# USB_Headers.net
KiCad netlist of a schematic drawn in Altium Designer
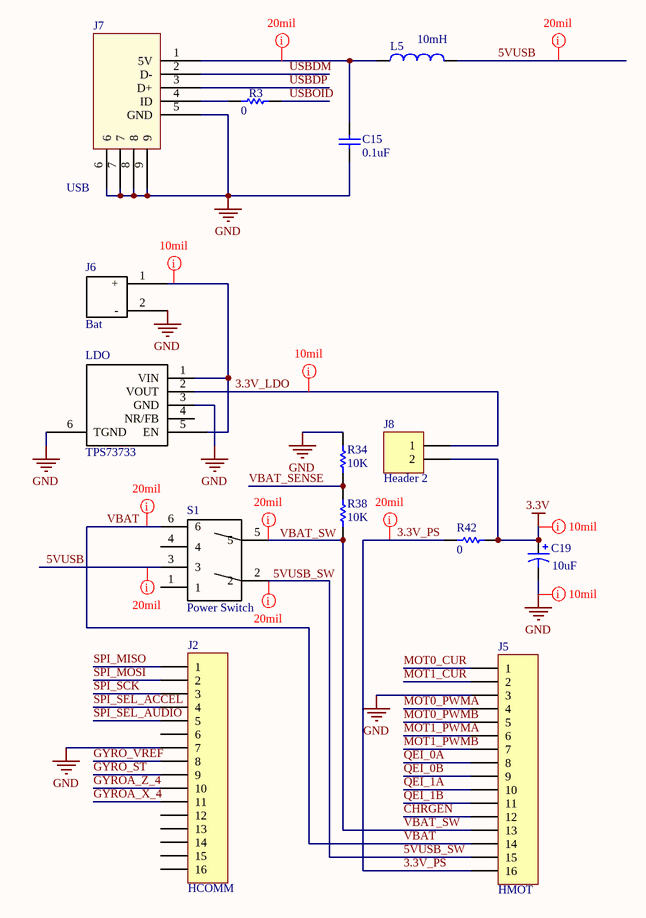
[diagram p0: USB_Headers.SchDoc]

(export (version "E")
  (design (tool "Eeschema 10.0.6"))
  (components
    (comp (ref "C15")
      (value "0.1uF")
      (footprint "CAPC1005L")
      (description "Capacitor")
      (fields (field (name "PUBLISHER") "Altium Limited"))
      (libsource (lib "Miscellaneous Devices") (part "Cap"))
    )
    (comp (ref "C19")
      (value "10uF")
      (footprint "CAPC3216L")
      (description "Polarized Capacitor (Surface Mount)")
      (fields (field (name "Comment") "Cap Pol3") (field (name "PUBLISHER") "Altium Limited"))
      (libsource (lib "Miscellaneous Devices") (part "Cap Pol3"))
    )
    (comp (ref "J2")
      (value "HCOMM")
      (footprint "HDR1X16")
      (description "Header, 16-Pin")
      (fields (field (name "PUBLISHER") "Altium Limited"))
      (libsource (lib "Miscellaneous Connectors") (part "Header 16"))
    )
    (comp (ref "J5")
      (value "HMOT")
      (footprint "HDR1X16")
      (description "Header, 16-Pin")
      (fields (field (name "PUBLISHER") "Altium Limited"))
      (libsource (lib "Miscellaneous Connectors") (part "Header 16"))
    )
    (comp (ref "J6")
      (value "Bat")
      (footprint "BatteryConnJST")
      (libsource (lib "mrone") (part "BatteryConnJST"))
    )
    (comp (ref "J7")
      (value "USB")
      (footprint "USB Minib (thru-hole)")
      (libsource (lib "mrone") (part "USB-ConnTH"))
    )
    (comp (ref "J8")
      (value "Header 2")
      (footprint "HDR1X2")
      (description "Header, 2-Pin")
      (fields (field (name "PUBLISHER") "Altium Limited"))
      (libsource (lib "Miscellaneous Connectors") (part "Header 2"))
    )
    (comp (ref "L5")
      (value "10mH")
      (footprint "INDC2012L")
      (description "Inductor")
      (fields (field (name "PUBLISHER") "Altium Limited"))
      (libsource (lib "Miscellaneous Devices") (part "Inductor"))
    )
    (comp (ref "LDO")
      (value "TPS73733")
      (footprint "SOT-223-5pin")
      (libsource (lib "mrone") (part "LDO33-TI-TPS73733"))
    )
    (comp (ref "R3")
      (value "0")
      (footprint "RESC1608L")
      (description "Resistor")
      (fields (field (name "PUBLISHER") "Altium Limited"))
      (libsource (lib "Miscellaneous Devices") (part "Res1"))
    )
    (comp (ref "R34")
      (value "10K")
      (footprint "RESC1608L")
      (description "Resistor")
      (fields (field (name "PUBLISHER") "Altium Limited"))
      (libsource (lib "Miscellaneous Devices") (part "Res1"))
    )
    (comp (ref "R38")
      (value "10K")
      (footprint "RESC1608L")
      (description "Resistor")
      (fields (field (name "PUBLISHER") "Altium Limited"))
      (libsource (lib "Miscellaneous Devices") (part "Res1"))
    )
    (comp (ref "R42")
      (value "0")
      (footprint "RESC3216L")
      (description "Resistor")
      (fields (field (name "PUBLISHER") "Altium Limited"))
      (libsource (lib "Miscellaneous Devices") (part "Res1"))
    )
    (comp (ref "S1")
      (value "Power Switch")
      (footprint "DPDTSwitch")
      (libsource (lib "mrone") (part "DPDTSwitch"))
    )
  )
  (nets
    (net (code "1") (name "/3.3V_LDO") (class "Default")
      (node (ref "J8") (pin "1") (pinfunction "1_1") (pintype "passive"))
      (node (ref "LDO") (pin "2") (pinfunction "VOUT_2") (pintype "passive"))
    )
    (net (code "2") (name "/3.3V_PS") (class "Default")
      (node (ref "J5") (pin "16") (pinfunction "16_16") (pintype "passive"))
      (node (ref "R42") (pin "1") (pinfunction "1_1") (pintype "passive"))
    )
    (net (code "3") (name "/5VUSB") (class "Default")
      (node (ref "L5") (pin "2") (pinfunction "2_2") (pintype "passive"))
      (node (ref "S1") (pin "3") (pinfunction "3_3") (pintype "passive"))
    )
    (net (code "4") (name "/5VUSB_SW") (class "Default")
      (node (ref "J5") (pin "15") (pinfunction "15_15") (pintype "passive"))
      (node (ref "S1") (pin "2") (pinfunction "2_2") (pintype "passive"))
    )
    (net (code "5") (name "/CHRGEN") (class "Default")
      (node (ref "J5") (pin "12") (pinfunction "12_12") (pintype "passive"))
    )
    (net (code "6") (name "/GYROA_X_4") (class "Default")
      (node (ref "J2") (pin "11") (pinfunction "11_11") (pintype "passive"))
    )
    (net (code "7") (name "/GYROA_Z_4") (class "Default")
      (node (ref "J2") (pin "10") (pinfunction "10_10") (pintype "passive"))
    )
    (net (code "8") (name "/GYRO_ST") (class "Default")
      (node (ref "J2") (pin "9") (pinfunction "9_9") (pintype "passive"))
    )
    (net (code "9") (name "/GYRO_VREF") (class "Default")
      (node (ref "J2") (pin "8") (pinfunction "8_8") (pintype "passive"))
    )
    (net (code "10") (name "/MOT0_CUR") (class "Default")
      (node (ref "J5") (pin "1") (pinfunction "1_1") (pintype "passive"))
    )
    (net (code "11") (name "/MOT0_PWMA") (class "Default")
      (node (ref "J5") (pin "4") (pinfunction "4_4") (pintype "passive"))
    )
    (net (code "12") (name "/MOT0_PWMB") (class "Default")
      (node (ref "J5") (pin "5") (pinfunction "5_5") (pintype "passive"))
    )
    (net (code "13") (name "/MOT1_CUR") (class "Default")
      (node (ref "J5") (pin "2") (pinfunction "2_2") (pintype "passive"))
    )
    (net (code "14") (name "/MOT1_PWMA") (class "Default")
      (node (ref "J5") (pin "6") (pinfunction "6_6") (pintype "passive"))
    )
    (net (code "15") (name "/MOT1_PWMB") (class "Default")
      (node (ref "J5") (pin "7") (pinfunction "7_7") (pintype "passive"))
    )
    (net (code "16") (name "/QEI_0A") (class "Default")
      (node (ref "J5") (pin "8") (pinfunction "8_8") (pintype "passive"))
    )
    (net (code "17") (name "/QEI_0B") (class "Default")
      (node (ref "J5") (pin "9") (pinfunction "9_9") (pintype "passive"))
    )
    (net (code "18") (name "/QEI_1A") (class "Default")
      (node (ref "J5") (pin "10") (pinfunction "10_10") (pintype "passive"))
    )
    (net (code "19") (name "/QEI_1B") (class "Default")
      (node (ref "J5") (pin "11") (pinfunction "11_11") (pintype "passive"))
    )
    (net (code "20") (name "/SPI_MISO") (class "Default")
      (node (ref "J2") (pin "1") (pinfunction "1_1") (pintype "passive"))
    )
    (net (code "21") (name "/SPI_MOSI") (class "Default")
      (node (ref "J2") (pin "2") (pinfunction "2_2") (pintype "passive"))
    )
    (net (code "22") (name "/SPI_SCK") (class "Default")
      (node (ref "J2") (pin "3") (pinfunction "3_3") (pintype "passive"))
    )
    (net (code "23") (name "/SPI_SEL_ACCEL") (class "Default")
      (node (ref "J2") (pin "4") (pinfunction "4_4") (pintype "passive"))
    )
    (net (code "24") (name "/SPI_SEL_AUDIO") (class "Default")
      (node (ref "J2") (pin "5") (pinfunction "5_5") (pintype "passive"))
    )
    (net (code "25") (name "/USBDM") (class "Default")
      (node (ref "J7") (pin "2") (pinfunction "D-_2") (pintype "passive"))
    )
    (net (code "26") (name "/USBDP") (class "Default")
      (node (ref "J7") (pin "3") (pinfunction "D+_3") (pintype "passive"))
    )
    (net (code "27") (name "/USBOID") (class "Default")
      (node (ref "R3") (pin "1") (pinfunction "1_1") (pintype "passive"))
    )
    (net (code "28") (name "/VBAT") (class "Default")
      (node (ref "J5") (pin "14") (pinfunction "14_14") (pintype "passive"))
      (node (ref "S1") (pin "6") (pinfunction "6_6") (pintype "passive"))
    )
    (net (code "29") (name "/VBAT_SENSE") (class "Default")
      (node (ref "R34") (pin "1") (pinfunction "1_1") (pintype "passive"))
      (node (ref "R38") (pin "2") (pinfunction "2_2") (pintype "passive"))
    )
    (net (code "30") (name "/VBAT_SW") (class "Default")
      (node (ref "J5") (pin "13") (pinfunction "13_13") (pintype "passive"))
      (node (ref "R38") (pin "1") (pinfunction "1_1") (pintype "passive"))
      (node (ref "S1") (pin "5") (pinfunction "5_5") (pintype "passive"))
    )
    (net (code "31") (name "3.3V") (class "Default")
      (node (ref "C19") (pin "1") (pinfunction "1_1") (pintype "passive"))
      (node (ref "J8") (pin "2") (pinfunction "2_2") (pintype "passive"))
      (node (ref "R42") (pin "2") (pinfunction "2_2") (pintype "passive"))
    )
    (net (code "32") (name "GND") (class "Default")
      (node (ref "C15") (pin "1") (pinfunction "1_1") (pintype "passive"))
      (node (ref "C19") (pin "2") (pinfunction "2_2") (pintype "passive"))
      (node (ref "J2") (pin "7") (pinfunction "7_7") (pintype "passive"))
      (node (ref "J5") (pin "3") (pinfunction "3_3") (pintype "passive"))
      (node (ref "J6") (pin "2") (pinfunction "-_2") (pintype "passive"))
      (node (ref "J7") (pin "5") (pinfunction "GND_5") (pintype "passive"))
      (node (ref "J7") (pin "6") (pinfunction "6_6") (pintype "passive"))
      (node (ref "J7") (pin "7") (pinfunction "7_7") (pintype "passive"))
      (node (ref "J7") (pin "8") (pinfunction "8_8") (pintype "passive"))
      (node (ref "J7") (pin "9") (pinfunction "9_9") (pintype "passive"))
      (node (ref "LDO") (pin "3") (pinfunction "GND_3") (pintype "passive"))
      (node (ref "LDO") (pin "6") (pinfunction "TGND_6") (pintype "passive"))
      (node (ref "R34") (pin "2") (pinfunction "2_2") (pintype "passive"))
    )
    (net (code "33") (name "Net-(J6-+)") (class "Default")
      (node (ref "J6") (pin "1") (pinfunction "+_1") (pintype "passive"))
      (node (ref "LDO") (pin "1") (pinfunction "VIN_1") (pintype "passive"))
      (node (ref "LDO") (pin "5") (pinfunction "EN_5") (pintype "passive"))
    )
    (net (code "34") (name "Net-(J7-5V)") (class "Default")
      (node (ref "C15") (pin "2") (pinfunction "2_2") (pintype "passive"))
      (node (ref "J7") (pin "1") (pinfunction "5V_1") (pintype "passive"))
      (node (ref "L5") (pin "1") (pinfunction "1_1") (pintype "passive"))
    )
    (net (code "35") (name "Net-(J7-ID)") (class "Default")
      (node (ref "J7") (pin "4") (pinfunction "ID_4") (pintype "passive"))
      (node (ref "R3") (pin "2") (pinfunction "2_2") (pintype "passive"))
    )
    (net (code "36") (name "unconnected-(J2-Pad6)") (class "Default")
      (node (ref "J2") (pin "6") (pinfunction "6_6") (pintype "passive"))
    )
    (net (code "37") (name "unconnected-(J2-Pad12)") (class "Default")
      (node (ref "J2") (pin "12") (pinfunction "12_12") (pintype "passive"))
    )
    (net (code "38") (name "unconnected-(J2-Pad13)") (class "Default")
      (node (ref "J2") (pin "13") (pinfunction "13_13") (pintype "passive"))
    )
    (net (code "39") (name "unconnected-(J2-Pad14)") (class "Default")
      (node (ref "J2") (pin "14") (pinfunction "14_14") (pintype "passive"))
    )
    (net (code "40") (name "unconnected-(J2-Pad15)") (class "Default")
      (node (ref "J2") (pin "15") (pinfunction "15_15") (pintype "passive"))
    )
    (net (code "41") (name "unconnected-(J2-Pad16)") (class "Default")
      (node (ref "J2") (pin "16") (pinfunction "16_16") (pintype "passive"))
    )
    (net (code "42") (name "unconnected-(LDO-NR{slash}FB-Pad4)") (class "Default")
      (node (ref "LDO") (pin "4") (pinfunction "NR/FB_4") (pintype "passive"))
    )
    (net (code "43") (name "unconnected-(S1-Pad1)") (class "Default")
      (node (ref "S1") (pin "1") (pinfunction "1_1") (pintype "passive"))
    )
    (net (code "44") (name "unconnected-(S1-Pad4)") (class "Default")
      (node (ref "S1") (pin "4") (pinfunction "4_4") (pintype "passive"))
    )
  )
)
